# voltage_board_-_itr2_-_V3.net
KiCad netlist of a schematic drawn in EAGLE
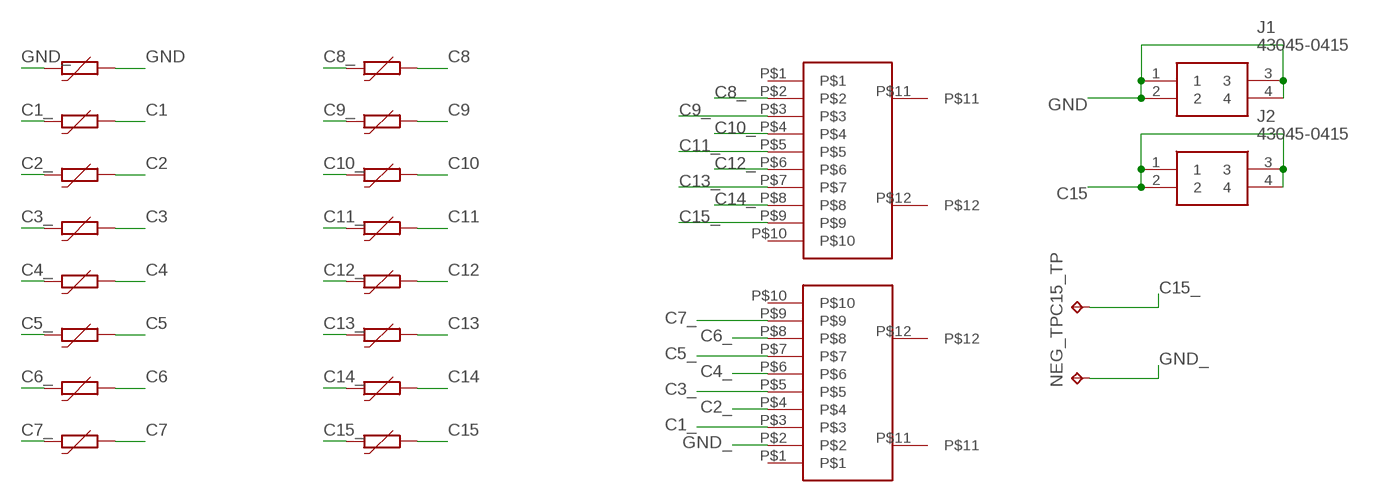
[diagram p0: schematic, sheet 1]

(export (version "E")
  (design (tool "Eeschema 10.0.6"))
  (components
    (comp (ref "C15_TP")
      (value "TPPAD1-13")
      (footprint "eagle-import:P1-13")
      (libsource (lib "eagle-import") (part "TPPAD1-13"))
    )
    (comp (ref "GND_F")
      (value "PTC-FUSE")
      (footprint "eagle-import:1206")
      (libsource (lib "eagle-import") (part "PTC-FUSE"))
    )
    (comp (ref "GND_F1")
      (value "PTC-FUSE")
      (footprint "eagle-import:1206")
      (libsource (lib "eagle-import") (part "PTC-FUSE"))
    )
    (comp (ref "GND_F2")
      (value "PTC-FUSE")
      (footprint "eagle-import:1206")
      (libsource (lib "eagle-import") (part "PTC-FUSE"))
    )
    (comp (ref "GND_F3")
      (value "PTC-FUSE")
      (footprint "eagle-import:1206")
      (libsource (lib "eagle-import") (part "PTC-FUSE"))
    )
    (comp (ref "GND_F4")
      (value "PTC-FUSE")
      (footprint "eagle-import:1206")
      (libsource (lib "eagle-import") (part "PTC-FUSE"))
    )
    (comp (ref "GND_F5")
      (value "PTC-FUSE")
      (footprint "eagle-import:1206")
      (libsource (lib "eagle-import") (part "PTC-FUSE"))
    )
    (comp (ref "GND_F6")
      (value "PTC-FUSE")
      (footprint "eagle-import:1206")
      (libsource (lib "eagle-import") (part "PTC-FUSE"))
    )
    (comp (ref "GND_F7")
      (value "PTC-FUSE")
      (footprint "eagle-import:1206")
      (libsource (lib "eagle-import") (part "PTC-FUSE"))
    )
    (comp (ref "GND_F8")
      (value "PTC-FUSE")
      (footprint "eagle-import:1206")
      (libsource (lib "eagle-import") (part "PTC-FUSE"))
    )
    (comp (ref "GND_F9")
      (value "PTC-FUSE")
      (footprint "eagle-import:1206")
      (libsource (lib "eagle-import") (part "PTC-FUSE"))
    )
    (comp (ref "GND_F10")
      (value "PTC-FUSE")
      (footprint "eagle-import:1206")
      (libsource (lib "eagle-import") (part "PTC-FUSE"))
    )
    (comp (ref "GND_F11")
      (value "PTC-FUSE")
      (footprint "eagle-import:1206")
      (libsource (lib "eagle-import") (part "PTC-FUSE"))
    )
    (comp (ref "GND_F12")
      (value "PTC-FUSE")
      (footprint "eagle-import:1206")
      (libsource (lib "eagle-import") (part "PTC-FUSE"))
    )
    (comp (ref "GND_F13")
      (value "PTC-FUSE")
      (footprint "eagle-import:1206")
      (libsource (lib "eagle-import") (part "PTC-FUSE"))
    )
    (comp (ref "GND_F14")
      (value "PTC-FUSE")
      (footprint "eagle-import:1206")
      (libsource (lib "eagle-import") (part "PTC-FUSE"))
    )
    (comp (ref "GND_F15")
      (value "PTC-FUSE")
      (footprint "eagle-import:1206")
      (libsource (lib "eagle-import") (part "PTC-FUSE"))
    )
    (comp (ref "J1")
      (value "43045-0415")
      (footprint "eagle-import:43045-04YY_15,16,17")
      (fields (field (name "MOUSER_PART_NUMBER") "538-43045-0415"))
      (libsource (lib "eagle-import") (part "43045-0415"))
    )
    (comp (ref "J2")
      (value "43045-0415")
      (footprint "eagle-import:43045-04YY_15,16,17")
      (fields (field (name "MOUSER_PART_NUMBER") "538-43045-0415"))
      (libsource (lib "eagle-import") (part "43045-0415"))
    )
    (comp (ref "NEG_TP")
      (value "TPPAD1-13")
      (footprint "eagle-import:P1-13")
      (libsource (lib "eagle-import") (part "TPPAD1-13"))
    )
    (comp (ref "U$37")
      (value "VERTICALBMS10")
      (footprint "eagle-import:VERTICALBMS10")
      (libsource (lib "eagle-import") (part "VERTICALBMS10"))
    )
    (comp (ref "U$38")
      (value "VERTICALBMS10")
      (footprint "eagle-import:VERTICALBMS10")
      (libsource (lib "eagle-import") (part "VERTICALBMS10"))
    )
  )
  (nets
    (net (code "1") (name "/C1") (class "Default")
      (node (ref "GND_F1") (pin "2") (pinfunction "2_2") (pintype "passive"))
    )
    (net (code "2") (name "/C1_") (class "Default")
      (node (ref "GND_F1") (pin "1") (pinfunction "1_1") (pintype "passive"))
      (node (ref "U$37") (pin "P$3") (pinfunction "P$3_P$3") (pintype "bidirectional"))
    )
    (net (code "3") (name "/C2") (class "Default")
      (node (ref "GND_F2") (pin "2") (pinfunction "2_2") (pintype "passive"))
    )
    (net (code "4") (name "/C2_") (class "Default")
      (node (ref "GND_F2") (pin "1") (pinfunction "1_1") (pintype "passive"))
      (node (ref "U$37") (pin "P$4") (pinfunction "P$4_P$4") (pintype "bidirectional"))
    )
    (net (code "5") (name "/C3") (class "Default")
      (node (ref "GND_F3") (pin "2") (pinfunction "2_2") (pintype "passive"))
    )
    (net (code "6") (name "/C3_") (class "Default")
      (node (ref "GND_F3") (pin "1") (pinfunction "1_1") (pintype "passive"))
      (node (ref "U$37") (pin "P$5") (pinfunction "P$5_P$5") (pintype "bidirectional"))
    )
    (net (code "7") (name "/C4") (class "Default")
      (node (ref "GND_F4") (pin "2") (pinfunction "2_2") (pintype "passive"))
    )
    (net (code "8") (name "/C4_") (class "Default")
      (node (ref "GND_F4") (pin "1") (pinfunction "1_1") (pintype "passive"))
      (node (ref "U$37") (pin "P$6") (pinfunction "P$6_P$6") (pintype "bidirectional"))
    )
    (net (code "9") (name "/C5") (class "Default")
      (node (ref "GND_F5") (pin "2") (pinfunction "2_2") (pintype "passive"))
    )
    (net (code "10") (name "/C5_") (class "Default")
      (node (ref "GND_F5") (pin "1") (pinfunction "1_1") (pintype "passive"))
      (node (ref "U$37") (pin "P$7") (pinfunction "P$7_P$7") (pintype "bidirectional"))
    )
    (net (code "11") (name "/C6") (class "Default")
      (node (ref "GND_F6") (pin "2") (pinfunction "2_2") (pintype "passive"))
    )
    (net (code "12") (name "/C6_") (class "Default")
      (node (ref "GND_F6") (pin "1") (pinfunction "1_1") (pintype "passive"))
      (node (ref "U$37") (pin "P$8") (pinfunction "P$8_P$8") (pintype "bidirectional"))
    )
    (net (code "13") (name "/C7") (class "Default")
      (node (ref "GND_F7") (pin "2") (pinfunction "2_2") (pintype "passive"))
    )
    (net (code "14") (name "/C7_") (class "Default")
      (node (ref "GND_F7") (pin "1") (pinfunction "1_1") (pintype "passive"))
      (node (ref "U$37") (pin "P$9") (pinfunction "P$9_P$9") (pintype "bidirectional"))
    )
    (net (code "15") (name "/C8") (class "Default")
      (node (ref "GND_F8") (pin "2") (pinfunction "2_2") (pintype "passive"))
    )
    (net (code "16") (name "/C8_") (class "Default")
      (node (ref "GND_F8") (pin "1") (pinfunction "1_1") (pintype "passive"))
      (node (ref "U$38") (pin "P$2") (pinfunction "P$2_P$2") (pintype "bidirectional"))
    )
    (net (code "17") (name "/C9") (class "Default")
      (node (ref "GND_F9") (pin "2") (pinfunction "2_2") (pintype "passive"))
    )
    (net (code "18") (name "/C9_") (class "Default")
      (node (ref "GND_F9") (pin "1") (pinfunction "1_1") (pintype "passive"))
      (node (ref "U$38") (pin "P$3") (pinfunction "P$3_P$3") (pintype "bidirectional"))
    )
    (net (code "19") (name "/C10") (class "Default")
      (node (ref "GND_F10") (pin "2") (pinfunction "2_2") (pintype "passive"))
    )
    (net (code "20") (name "/C10_") (class "Default")
      (node (ref "GND_F10") (pin "1") (pinfunction "1_1") (pintype "passive"))
      (node (ref "U$38") (pin "P$4") (pinfunction "P$4_P$4") (pintype "bidirectional"))
    )
    (net (code "21") (name "/C11") (class "Default")
      (node (ref "GND_F11") (pin "2") (pinfunction "2_2") (pintype "passive"))
    )
    (net (code "22") (name "/C11_") (class "Default")
      (node (ref "GND_F11") (pin "1") (pinfunction "1_1") (pintype "passive"))
      (node (ref "U$38") (pin "P$5") (pinfunction "P$5_P$5") (pintype "bidirectional"))
    )
    (net (code "23") (name "/C12") (class "Default")
      (node (ref "GND_F12") (pin "2") (pinfunction "2_2") (pintype "passive"))
    )
    (net (code "24") (name "/C12_") (class "Default")
      (node (ref "GND_F12") (pin "1") (pinfunction "1_1") (pintype "passive"))
      (node (ref "U$38") (pin "P$6") (pinfunction "P$6_P$6") (pintype "bidirectional"))
    )
    (net (code "25") (name "/C13") (class "Default")
      (node (ref "GND_F13") (pin "2") (pinfunction "2_2") (pintype "passive"))
    )
    (net (code "26") (name "/C13_") (class "Default")
      (node (ref "GND_F13") (pin "1") (pinfunction "1_1") (pintype "passive"))
      (node (ref "U$38") (pin "P$7") (pinfunction "P$7_P$7") (pintype "bidirectional"))
    )
    (net (code "27") (name "/C14") (class "Default")
      (node (ref "GND_F14") (pin "2") (pinfunction "2_2") (pintype "passive"))
    )
    (net (code "28") (name "/C14_") (class "Default")
      (node (ref "GND_F14") (pin "1") (pinfunction "1_1") (pintype "passive"))
      (node (ref "U$38") (pin "P$8") (pinfunction "P$8_P$8") (pintype "bidirectional"))
    )
    (net (code "29") (name "/C15") (class "Default")
      (node (ref "GND_F15") (pin "2") (pinfunction "2_2") (pintype "passive"))
      (node (ref "J2") (pin "1") (pinfunction "1_1") (pintype "bidirectional"))
      (node (ref "J2") (pin "2") (pinfunction "2_2") (pintype "bidirectional"))
      (node (ref "J2") (pin "3") (pinfunction "3_3") (pintype "bidirectional"))
      (node (ref "J2") (pin "4") (pinfunction "4_4") (pintype "bidirectional"))
    )
    (net (code "30") (name "/C15_") (class "Default")
      (node (ref "C15_TP") (pin "TP") (pinfunction "TP_TP") (pintype "input"))
      (node (ref "GND_F15") (pin "1") (pinfunction "1_1") (pintype "passive"))
      (node (ref "U$38") (pin "P$9") (pinfunction "P$9_P$9") (pintype "bidirectional"))
    )
    (net (code "31") (name "/GND") (class "Default")
      (node (ref "GND_F") (pin "2") (pinfunction "2_2") (pintype "passive"))
      (node (ref "J1") (pin "1") (pinfunction "1_1") (pintype "bidirectional"))
      (node (ref "J1") (pin "2") (pinfunction "2_2") (pintype "bidirectional"))
      (node (ref "J1") (pin "3") (pinfunction "3_3") (pintype "bidirectional"))
      (node (ref "J1") (pin "4") (pinfunction "4_4") (pintype "bidirectional"))
    )
    (net (code "32") (name "/GND_") (class "Default")
      (node (ref "GND_F") (pin "1") (pinfunction "1_1") (pintype "passive"))
      (node (ref "NEG_TP") (pin "TP") (pinfunction "TP_TP") (pintype "input"))
      (node (ref "U$37") (pin "P$2") (pinfunction "P$2_P$2") (pintype "bidirectional"))
    )
    (net (code "33") (name "unconnected-(U$37-PadP$1)") (class "Default")
      (node (ref "U$37") (pin "P$1") (pinfunction "P$1_P$1") (pintype "bidirectional"))
    )
    (net (code "34") (name "unconnected-(U$37-PadP$10)") (class "Default")
      (node (ref "U$37") (pin "P$10") (pinfunction "P$10_P$10") (pintype "bidirectional"))
    )
    (net (code "35") (name "unconnected-(U$37-PadP$11)") (class "Default")
      (node (ref "U$37") (pin "P$11") (pinfunction "P$11_P$11") (pintype "bidirectional"))
    )
    (net (code "36") (name "unconnected-(U$37-PadP$12)") (class "Default")
      (node (ref "U$37") (pin "P$12") (pinfunction "P$12_P$12") (pintype "bidirectional"))
    )
    (net (code "37") (name "unconnected-(U$38-PadP$1)") (class "Default")
      (node (ref "U$38") (pin "P$1") (pinfunction "P$1_P$1") (pintype "bidirectional"))
    )
    (net (code "38") (name "unconnected-(U$38-PadP$10)") (class "Default")
      (node (ref "U$38") (pin "P$10") (pinfunction "P$10_P$10") (pintype "bidirectional"))
    )
    (net (code "39") (name "unconnected-(U$38-PadP$11)") (class "Default")
      (node (ref "U$38") (pin "P$11") (pinfunction "P$11_P$11") (pintype "bidirectional"))
    )
    (net (code "40") (name "unconnected-(U$38-PadP$12)") (class "Default")
      (node (ref "U$38") (pin "P$12") (pinfunction "P$12_P$12") (pintype "bidirectional"))
    )
  )
)
